# 1__Power.net
KiCad netlist of a schematic drawn in Altium Designer
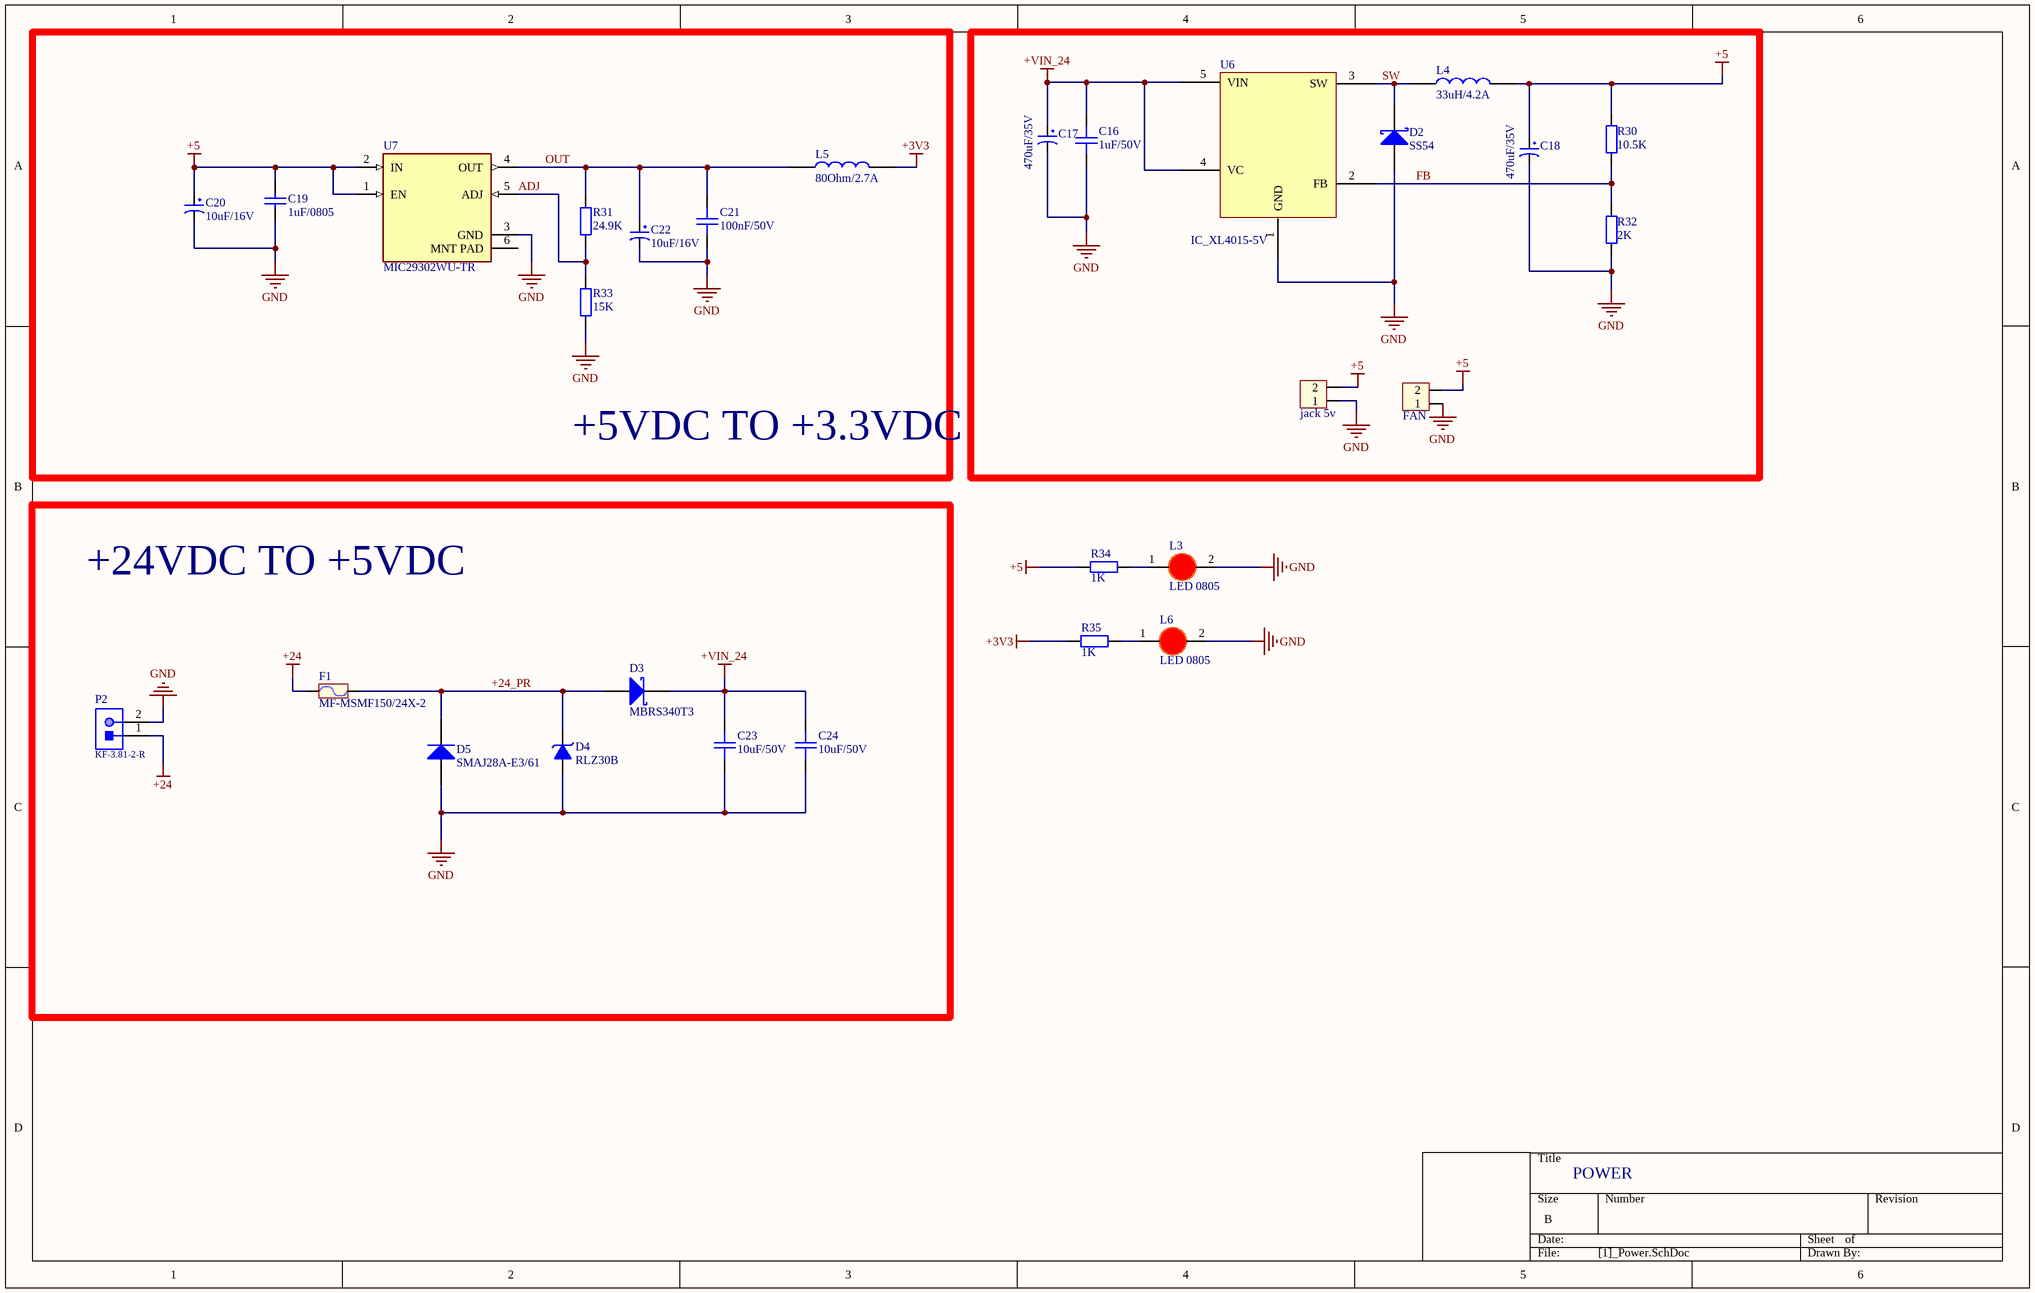
[diagram p0: [1]_Power.SchDoc]

(export (version "E")
  (design (tool "Eeschema 10.0.6"))
  (components
    (comp (ref "C16")
      (value "1uF/50V")
      (footprint "1206")
      (description "CAP CER 10uF/50V 1206")
      (fields (field (name "MANUFACTURER") "Samsung") (field (name "PART NUMBER") "C1206"))
      (libsource (lib "COMPONENT_INS") (part "CAP_CER_1206_1uF"))
    )
    (comp (ref "C17")
      (value "470uF/35V")
      (footprint "CAP_10_10")
      (description "CAP ALUM 33uF/100V 10x10.5")
      (fields (field (name "MANUFACTURER") "OEM") (field (name "PART NUMBER") "ALUM_33uF"))
      (libsource (lib "COMPONENT_INS") (part "CAP_ALUM_10_10_33uF/100V"))
    )
    (comp (ref "C18")
      (value "470uF/35V")
      (footprint "CAP_10_10")
      (description "CAP ALUM 33uF/100V 10x10.5")
      (fields (field (name "MANUFACTURER") "OEM") (field (name "PART NUMBER") "ALUM_33uF"))
      (libsource (lib "COMPONENT_INS") (part "CAP_ALUM_10_10_33uF/100V"))
    )
    (comp (ref "C19")
      (value "1uF/0805")
      (footprint "tu 0805")
      (description "Dán")
      (libsource (lib "Altium_Lib_by_KhueNguyenCreator") (part "Tu 0805 104 50V 10%"))
    )
    (comp (ref "C20")
      (value "10uF/16V")
      (footprint "2312")
      (description "CAP TANT 100uF/10V 2312")
      (fields (field (name "MANUFACTURER") "AVX") (field (name "PART NUMBER") "TAJC107K010RNJ"))
      (libsource (lib "COMPONENT_INS") (part "CAP_TANT_2312_100uF"))
    )
    (comp (ref "C21")
      (value "100nF/50V")
      (footprint "C0805")
      (description "CAP CER 100nF/50V 0805")
      (fields (field (name "MANUFACTURER") "Samsung") (field (name "PART NUMBER") "C0805"))
      (libsource (lib "COMPONENT_INS") (part "CAP_CER_0805_100nF"))
    )
    (comp (ref "C22")
      (value "10uF/16V")
      (footprint "2312")
      (description "CAP TANT 100uF/10V 2312")
      (fields (field (name "MANUFACTURER") "AVX") (field (name "PART NUMBER") "TAJC107K010RNJ"))
      (libsource (lib "COMPONENT_INS") (part "CAP_TANT_2312_100uF"))
    )
    (comp (ref "C23")
      (value "10uF/50V")
      (footprint "1210")
      (description "CAP CER 10uF/50V 1210")
      (fields (field (name "MANUFACTURER") "Yageo") (field (name "PART NUMBER") "C1210"))
      (libsource (lib "COMPONENT_INS") (part "CAP_CER_1210_10uF"))
    )
    (comp (ref "C24")
      (value "10uF/50V")
      (footprint "1210")
      (description "CAP CER 10uF/50V 1210")
      (fields (field (name "MANUFACTURER") "Yageo") (field (name "PART NUMBER") "C1210"))
      (libsource (lib "COMPONENT_INS") (part "CAP_CER_1210_10uF"))
    )
    (comp (ref "D2")
      (value "SS54")
      (footprint "DO-SMB-2")
      (description "DIODE SCHOTTKY 5A 40V SMB")
      (fields (field (name "MANUFACTURER") "Vishay"))
      (libsource (lib "COMPONENT_INS") (part "DIO_SS54"))
    )
    (comp (ref "D3")
      (value "MBRS340T3")
      (footprint "DO214AB_SMC")
      (description "DIODE SCHOTTKY 4A 40V SMC DO-214AB")
      (fields (field (name "MANUFACTURER") "Fairchild") (field (name "PART NUMBER") "SS14"))
      (libsource (lib "COMPONENT_INS") (part "DIO_MBRS340T3"))
    )
    (comp (ref "D4")
      (value "RLZ30B")
      (footprint "SOD_80")
      (description "ZMM15 15V 500mW SMD SOD-80")
      (fields (field (name "MANUFACTURER") "On Semiconductor") (field (name "PART NUMBER") "ZMM15"))
      (libsource (lib "COMPONENT_INS") (part "DIO_ZMM15"))
    )
    (comp (ref "D5")
      (value "SMAJ28A-E3/61")
      (footprint "VISH-DO-214AC-2_L")
      (fields (field (name "MANUFACTURER") "Vishay Semiconductor"))
      (libsource (lib "Altium Content Vault") (part "VISH-K1A2-2"))
    )
    (comp (ref "F1")
      (value "MF-MSMF150/24X-2")
      (footprint "1812")
      (description "MF-MSMF250/16 16V 2.5A1812")
      (fields (field (name "MANUFACTURER") "Bourns") (field (name "PART NUMBER") "1812"))
      (libsource (lib "COMPONENT_INS") (part "FUSE_16V_2.5A"))
    )
    (comp (ref "H1")
      (value "jack 5v")
      (footprint "VH3.96M-2")
      (description "Cắm")
      (libsource (lib "Altium_Lib_by_KhueNguyenCreator") (part "Header 2P VH3.96 Duc Thang"))
    )
    (comp (ref "H2")
      (value "FAN")
      (footprint "XH2.54M-2")
      (description "Cắm")
      (libsource (lib "Altium_Lib_by_KhueNguyenCreator") (part "Header 2P 2.54 Duc Thang"))
    )
    (comp (ref "L3")
      (value "LED 0805")
      (footprint "LED-0805-Red")
      (description "Dán")
      (libsource (lib "Altium_Lib_by_KhueNguyenCreator") (part "LED 0805 Do"))
    )
    (comp (ref "L4")
      (value "33uH/4.2A")
      (footprint "IND-12_12_8")
      (description "CDRH127 IND 33uH 4.2A 12x12x8")
      (fields (field (name "MANUFACTURER") "OEM") (field (name "PART NUMBER") "CDRH127"))
      (libsource (lib "COMPONENT_INS") (part "IND_33uH_4.2A_1280"))
    )
    (comp (ref "L5")
      (value "80Ohm/2.7A")
      (footprint "FER-0805 (2012)")
      (description "FERRITE BEAD 2.7A 80 OHM 0805")
      (fields (field (name "MANUFACTURER") "Taiyo Yuden") (field (name "PART NUMBER") "FBMH2012HM800-T"))
      (libsource (lib "COMPONENT_INS") (part "FERRITE_BEAD_2.7A_80"))
    )
    (comp (ref "L6")
      (value "LED 0805")
      (footprint "LED-0805-Red")
      (description "Dán")
      (libsource (lib "Altium_Lib_by_KhueNguyenCreator") (part "LED 0805 Do"))
    )
    (comp (ref "P2")
      (value "KF-3.81-2-R")
      (footprint "691322310002")
      (description "Serie 322 - 3.81mm Horizontal PCB Header WR-TBL, 2 pin")
      (fields
        (field (name "PART NUMBER") "691322310002")
        (field (name "MANUFACTURER") "Wurth Elektronik")
        (field (name "PUBLISHER") "WurthElektronik")
      )
      (libsource (lib "Altium Content Vault") (part "WE-CN-1P-M-R2"))
    )
    (comp (ref "R30")
      (value "10.5K")
      (footprint "R1206")
      (description "RES 1206 3.3K")
      (fields (field (name "MANUFACTURER") "OEM") (field (name "PART NUMBER") "R1206"))
      (libsource (lib "COMPONENT_INS") (part "RES_1206_3.3K"))
    )
    (comp (ref "R31")
      (value "24.9K")
      (footprint "tro smd 0805")
      (description "Dán")
      (libsource (lib "Altium_Lib_by_KhueNguyenCreator") (part "Tro 0805 5% 20k"))
    )
    (comp (ref "R32")
      (value "2K")
      (footprint "R0805")
      (description "RES 0805 0K")
      (fields (field (name "MANUFACTURER") "OEM") (field (name "PART NUMBER") "R0805"))
      (libsource (lib "") (part "RES_0805_0K_1"))
    )
    (comp (ref "R33")
      (value "15K")
      (footprint "tro smd 0805")
      (description "Dán")
      (libsource (lib "Altium_Lib_by_KhueNguyenCreator") (part "Tro 0805 5% 47k"))
    )
    (comp (ref "R34")
      (value "1K")
      (footprint "R0805")
      (description "RES 0805 0K")
      (fields (field (name "MANUFACTURER") "OEM") (field (name "PART NUMBER") "R0805"))
      (libsource (lib "COMPONENT_INS") (part "RES_0805_0K"))
    )
    (comp (ref "R35")
      (value "1K")
      (footprint "R0805")
      (description "RES 0805 0K")
      (fields (field (name "MANUFACTURER") "OEM") (field (name "PART NUMBER") "R0805"))
      (libsource (lib "COMPONENT_INS") (part "RES_0805_0K"))
    )
    (comp (ref "U6")
      (value "IC_XL4015-5V")
      (footprint "TO-263-5")
      (description "XL4015E1 Buck converter 5A TO 263")
      (fields (field (name "MANUFACTURER") "XLSEMI") (field (name "PART NUMBER") "XL4015E1"))
      (libsource (lib "COMPONENT_INS") (part "IC_XL4015-5V"))
    )
    (comp (ref "U7")
      (value "MIC29302WU-TR")
      (footprint "FP-C04-012-MFG")
      (description "IC REG LINEAR POS ADJ 3A TO263-5")
      (fields
        (field (name "MANUFACTURER") "Microchip")
        (field (name "OCTOPART") "https://octopart.com/mic29302wu-tr-microchip-66801318")
      )
      (libsource (lib "Altium Content Vault") (part "0db40f55fda0e91d0d14528974a446d"))
    )
  )
  (nets
    (net (code "1") (name "+3V3") (class "Default")
      (node (ref "L5") (pin "2") (pinfunction "2_2") (pintype "passive"))
      (node (ref "R35") (pin "2") (pinfunction "2_2") (pintype "passive"))
    )
    (net (code "2") (name "+5") (class "Default")
      (node (ref "C18") (pin "1") (pinfunction "1_1") (pintype "passive"))
      (node (ref "C19") (pin "1") (pinfunction "1_1") (pintype "passive"))
      (node (ref "C20") (pin "1") (pinfunction "1_1") (pintype "passive"))
      (node (ref "H1") (pin "2") (pinfunction "2_2") (pintype "passive"))
      (node (ref "H2") (pin "2") (pinfunction "2_2") (pintype "passive"))
      (node (ref "L4") (pin "2") (pinfunction "2_2") (pintype "passive"))
      (node (ref "R30") (pin "1") (pinfunction "1_1") (pintype "passive"))
      (node (ref "R34") (pin "2") (pinfunction "2_2") (pintype "passive"))
      (node (ref "U7") (pin "1") (pinfunction "EN_1") (pintype "input"))
      (node (ref "U7") (pin "2") (pinfunction "IN_2") (pintype "input"))
    )
    (net (code "3") (name "+24") (class "Default")
      (node (ref "F1") (pin "1") (pinfunction "1_1") (pintype "passive"))
      (node (ref "P2") (pin "1") (pinfunction "1_1") (pintype "passive"))
    )
    (net (code "4") (name "+VIN_24") (class "Default")
      (node (ref "C16") (pin "2") (pinfunction "2_2") (pintype "passive"))
      (node (ref "C17") (pin "1") (pinfunction "1_1") (pintype "passive"))
      (node (ref "C23") (pin "2") (pinfunction "2_2") (pintype "passive"))
      (node (ref "C24") (pin "2") (pinfunction "2_2") (pintype "passive"))
      (node (ref "D3") (pin "2") (pinfunction "K_2") (pintype "passive"))
      (node (ref "U6") (pin "4") (pinfunction "VC_4") (pintype "passive"))
      (node (ref "U6") (pin "5") (pinfunction "VIN_5") (pintype "passive"))
    )
    (net (code "5") (name "/+24_PR") (class "Default")
      (node (ref "D3") (pin "1") (pinfunction "A_1") (pintype "passive"))
      (node (ref "D4") (pin "2") (pinfunction "K_2") (pintype "passive"))
      (node (ref "D5") (pin "1") (pinfunction "K_1") (pintype "passive"))
      (node (ref "F1") (pin "2") (pinfunction "2_2") (pintype "passive"))
    )
    (net (code "6") (name "/ADJ") (class "Default")
      (node (ref "R31") (pin "1") (pinfunction "1_1") (pintype "passive"))
      (node (ref "R33") (pin "2") (pinfunction "2_2") (pintype "passive"))
      (node (ref "U7") (pin "5") (pinfunction "ADJ_5") (pintype "input"))
    )
    (net (code "7") (name "/FB") (class "Default")
      (node (ref "R30") (pin "2") (pinfunction "2_2") (pintype "passive"))
      (node (ref "R32") (pin "2") (pinfunction "2_2") (pintype "passive"))
      (node (ref "U6") (pin "2") (pinfunction "FB_2") (pintype "passive"))
    )
    (net (code "8") (name "/OUT") (class "Default")
      (node (ref "C21") (pin "2") (pinfunction "2_2") (pintype "passive"))
      (node (ref "C22") (pin "1") (pinfunction "1_1") (pintype "passive"))
      (node (ref "L5") (pin "1") (pinfunction "1_1") (pintype "passive"))
      (node (ref "R31") (pin "2") (pinfunction "2_2") (pintype "passive"))
      (node (ref "U7") (pin "4") (pinfunction "OUT_4") (pintype "output"))
    )
    (net (code "9") (name "/SW") (class "Default")
      (node (ref "D2") (pin "2") (pinfunction "K_2") (pintype "passive"))
      (node (ref "L4") (pin "1") (pinfunction "1_1") (pintype "passive"))
      (node (ref "U6") (pin "3") (pinfunction "SW_3") (pintype "passive"))
    )
    (net (code "10") (name "GND") (class "Default")
      (node (ref "C16") (pin "1") (pinfunction "1_1") (pintype "passive"))
      (node (ref "C17") (pin "2") (pinfunction "2_2") (pintype "passive"))
      (node (ref "C18") (pin "2") (pinfunction "2_2") (pintype "passive"))
      (node (ref "C19") (pin "2") (pinfunction "2_2") (pintype "passive"))
      (node (ref "C20") (pin "2") (pinfunction "2_2") (pintype "passive"))
      (node (ref "C21") (pin "1") (pinfunction "1_1") (pintype "passive"))
      (node (ref "C22") (pin "2") (pinfunction "2_2") (pintype "passive"))
      (node (ref "C23") (pin "1") (pinfunction "1_1") (pintype "passive"))
      (node (ref "C24") (pin "1") (pinfunction "1_1") (pintype "passive"))
      (node (ref "D2") (pin "1") (pinfunction "A_1") (pintype "passive"))
      (node (ref "D4") (pin "1") (pinfunction "A_1") (pintype "passive"))
      (node (ref "D5") (pin "2") (pinfunction "A_2") (pintype "passive"))
      (node (ref "H1") (pin "1") (pinfunction "1_1") (pintype "passive"))
      (node (ref "H2") (pin "1") (pinfunction "1_1") (pintype "passive"))
      (node (ref "L3") (pin "2") (pinfunction "K_2") (pintype "passive"))
      (node (ref "L6") (pin "2") (pinfunction "K_2") (pintype "passive"))
      (node (ref "P2") (pin "2") (pinfunction "2_2") (pintype "passive"))
      (node (ref "R32") (pin "1") (pinfunction "1_1") (pintype "passive"))
      (node (ref "R33") (pin "1") (pinfunction "1_1") (pintype "passive"))
      (node (ref "U6") (pin "1") (pinfunction "GND_1") (pintype "passive"))
      (node (ref "U7") (pin "3") (pinfunction "GND_3") (pintype "power_in"))
    )
    (net (code "11") (name "Net-(L3-A)") (class "Default")
      (node (ref "L3") (pin "1") (pinfunction "A_1") (pintype "passive"))
      (node (ref "R34") (pin "1") (pinfunction "1_1") (pintype "passive"))
    )
    (net (code "12") (name "Net-(L6-A)") (class "Default")
      (node (ref "L6") (pin "1") (pinfunction "A_1") (pintype "passive"))
      (node (ref "R35") (pin "1") (pinfunction "1_1") (pintype "passive"))
    )
    (net (code "13") (name "unconnected-(U7-MNT_PAD-Pad6)") (class "Default")
      (node (ref "U7") (pin "6") (pinfunction "MNT_PAD_6") (pintype "passive"))
    )
  )
)
